# MySensors_PIR.net
KiCad netlist of a schematic drawn in EAGLE
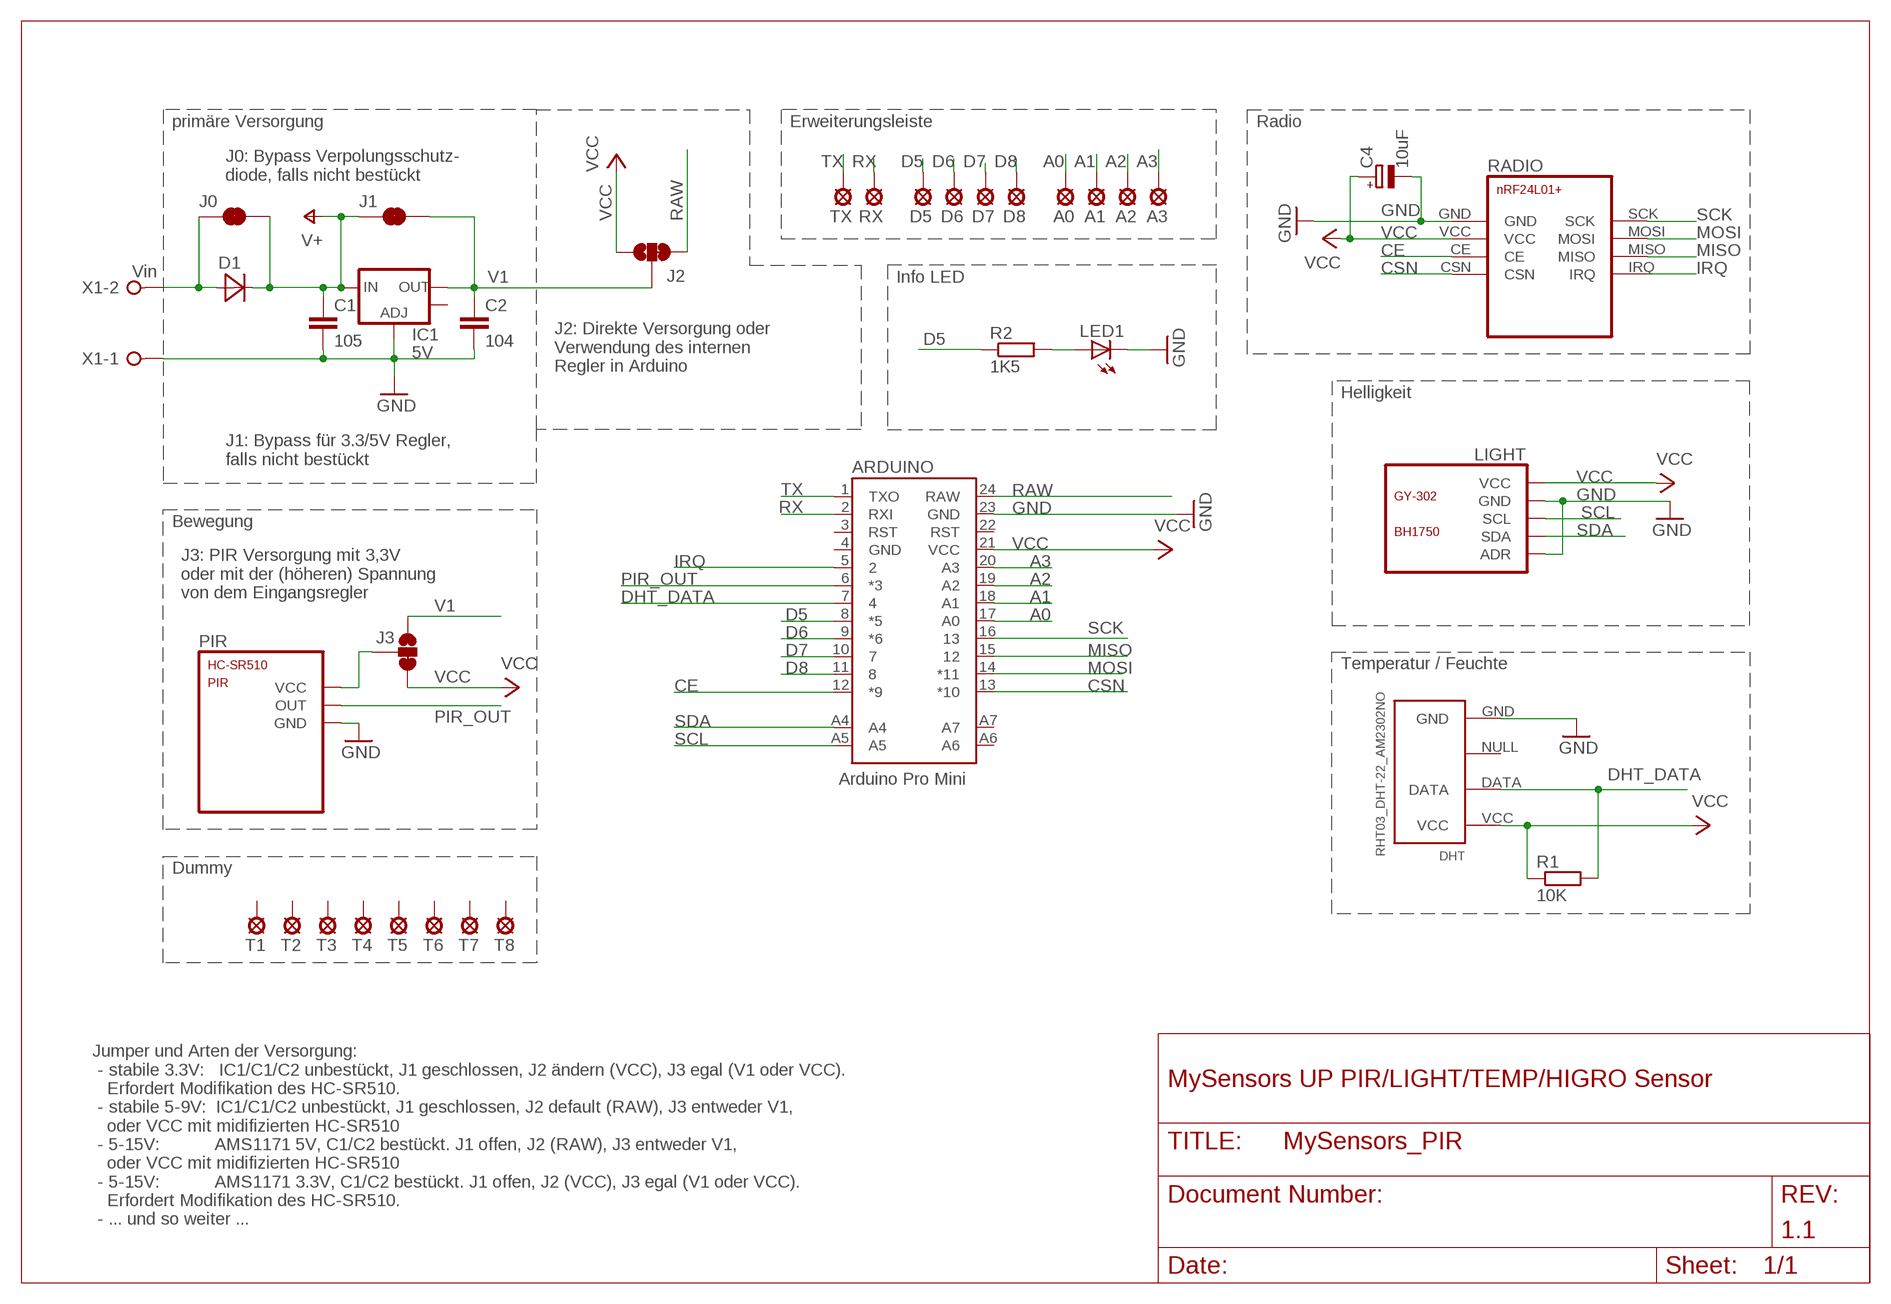
[diagram p0: schematic, sheet 1]

(export (version "E")
  (design (tool "Eeschema 10.0.6"))
  (components
    (comp (ref "A0")
      (value "LSP10")
      (footprint "eagle-import:LSP10")
      (libsource (lib "eagle-import") (part "LSP10"))
    )
    (comp (ref "A1")
      (value "LSP10")
      (footprint "eagle-import:LSP10")
      (libsource (lib "eagle-import") (part "LSP10"))
    )
    (comp (ref "A2")
      (value "LSP10")
      (footprint "eagle-import:LSP10")
      (libsource (lib "eagle-import") (part "LSP10"))
    )
    (comp (ref "A3")
      (value "LSP10")
      (footprint "eagle-import:LSP10")
      (libsource (lib "eagle-import") (part "LSP10"))
    )
    (comp (ref "ARDUINO")
      (value "ARDUINO_PRO_MININO")
      (footprint "eagle-import:ARDUINO_PRO_MINI_O")
      (libsource (lib "eagle-import") (part "ARDUINO_PRO_MININO"))
    )
    (comp (ref "C1")
      (value "105")
      (footprint "eagle-import:C025-025X050")
      (libsource (lib "eagle-import") (part "C-EU025-025X050"))
    )
    (comp (ref "C2")
      (value "104")
      (footprint "eagle-import:C025-025X050")
      (libsource (lib "eagle-import") (part "C-EU025-025X050"))
    )
    (comp (ref "C4")
      (value "10uF")
      (footprint "eagle-import:E2,5-6E")
      (libsource (lib "eagle-import") (part "CPOL-EUE2,5-6E"))
    )
    (comp (ref "D1")
      (value "DIODE2.5U")
      (footprint "eagle-import:DIODE2.5U")
      (libsource (lib "eagle-import") (part "DIODE2.5U"))
    )
    (comp (ref "D5")
      (value "LSP10")
      (footprint "eagle-import:LSP10")
      (libsource (lib "eagle-import") (part "LSP10"))
    )
    (comp (ref "D6")
      (value "LSP10")
      (footprint "eagle-import:LSP10")
      (libsource (lib "eagle-import") (part "LSP10"))
    )
    (comp (ref "D7")
      (value "LSP10")
      (footprint "eagle-import:LSP10")
      (libsource (lib "eagle-import") (part "LSP10"))
    )
    (comp (ref "D8")
      (value "LSP10")
      (footprint "eagle-import:LSP10")
      (libsource (lib "eagle-import") (part "LSP10"))
    )
    (comp (ref "DHT")
      (value "RHT03_DHT-22_AM2302NO")
      (footprint "eagle-import:RHT03_DHT-22_RA_O")
      (libsource (lib "eagle-import") (part "RHT03_DHT-22_AM2302NO"))
    )
    (comp (ref "IC1")
      (value "5V")
      (footprint "eagle-import:SOT223")
      (libsource (lib "eagle-import") (part "V_REG_LM1117SOT223"))
    )
    (comp (ref "J0")
      (value "JUMPER-PAD-2-NC_BY_TRACE")
      (footprint "eagle-import:PAD-JUMPER-2-NC_BY_TRACE_YES_SILK")
      (libsource (lib "eagle-import") (part "JUMPER-PAD-2-NC_BY_TRACE"))
    )
    (comp (ref "J1")
      (value "JUMPER-PAD-2-NC_BY_TRACE")
      (footprint "eagle-import:PAD-JUMPER-2-NC_BY_TRACE_YES_SILK")
      (libsource (lib "eagle-import") (part "JUMPER-PAD-2-NC_BY_TRACE"))
    )
    (comp (ref "J2")
      (value "JUMPER-PAD-3-2OF3_NC_BY_TRACE_SMALL")
      (footprint "eagle-import:PAD-JUMPER-3-2OF3_NC_BY_TRACE_YES_SILK_FULL_BOX")
      (libsource (lib "eagle-import") (part "JUMPER-PAD-3-2OF3_NC_BY_TRACE_SMALL"))
    )
    (comp (ref "J3")
      (value "JUMPER-PAD-3-2OF3_NC_BY_TRACE_SMALL")
      (footprint "eagle-import:PAD-JUMPER-3-2OF3_NC_BY_TRACE_YES_SILK_FULL_BOX")
      (libsource (lib "eagle-import") (part "JUMPER-PAD-3-2OF3_NC_BY_TRACE_SMALL"))
    )
    (comp (ref "LED1")
      (value "UNI_LED_3MM+SMD")
      (footprint "eagle-import:LED3MM")
      (libsource (lib "eagle-import") (part "UNI_LED_3MM+SMD"))
    )
    (comp (ref "LIGHT")
      (value "GY-302")
      (footprint "eagle-import:GY-302")
      (libsource (lib "eagle-import") (part "GY-302"))
    )
    (comp (ref "PIR")
      (value "HC-SR501")
      (footprint "eagle-import:HC-SR501")
      (libsource (lib "eagle-import") (part "HC-SR501"))
    )
    (comp (ref "R1")
      (value "10K")
      (footprint "eagle-import:0204V")
      (libsource (lib "eagle-import") (part "R-EU_0204/2V"))
    )
    (comp (ref "R2")
      (value "1K5")
      (footprint "eagle-import:0204V")
      (libsource (lib "eagle-import") (part "R-EU_0204/2V"))
    )
    (comp (ref "RADIO")
      (value "NRF24L01+")
      (footprint "eagle-import:NRF24L01+")
      (libsource (lib "eagle-import") (part "NRF24L01+"))
    )
    (comp (ref "RX")
      (value "LSP10")
      (footprint "eagle-import:LSP10")
      (libsource (lib "eagle-import") (part "LSP10"))
    )
    (comp (ref "T1")
      (value "LSP10")
      (footprint "eagle-import:LSP10")
      (libsource (lib "eagle-import") (part "LSP10"))
    )
    (comp (ref "T2")
      (value "LSP10")
      (footprint "eagle-import:LSP10")
      (libsource (lib "eagle-import") (part "LSP10"))
    )
    (comp (ref "T3")
      (value "LSP10")
      (footprint "eagle-import:LSP10")
      (libsource (lib "eagle-import") (part "LSP10"))
    )
    (comp (ref "T4")
      (value "LSP10")
      (footprint "eagle-import:LSP10")
      (libsource (lib "eagle-import") (part "LSP10"))
    )
    (comp (ref "T5")
      (value "LSP10")
      (footprint "eagle-import:LSP10")
      (libsource (lib "eagle-import") (part "LSP10"))
    )
    (comp (ref "T6")
      (value "LSP10")
      (footprint "eagle-import:LSP10")
      (libsource (lib "eagle-import") (part "LSP10"))
    )
    (comp (ref "T7")
      (value "LSP10")
      (footprint "eagle-import:LSP10")
      (libsource (lib "eagle-import") (part "LSP10"))
    )
    (comp (ref "T8")
      (value "LSP10")
      (footprint "eagle-import:LSP10")
      (libsource (lib "eagle-import") (part "LSP10"))
    )
    (comp (ref "TX")
      (value "LSP10")
      (footprint "eagle-import:LSP10")
      (libsource (lib "eagle-import") (part "LSP10"))
    )
    (comp (ref "X1")
      (value "Vin")
      (footprint "eagle-import:W237-132")
      (libsource (lib "eagle-import") (part "W237-02P"))
    )
  )
  (nets
    (net (code "1") (name "/A0") (class "Default")
      (node (ref "A0") (pin "1") (pinfunction "MP_1") (pintype "passive"))
      (node (ref "ARDUINO") (pin "17") (pinfunction "A0_17") (pintype "bidirectional"))
    )
    (net (code "2") (name "/A1") (class "Default")
      (node (ref "A1") (pin "1") (pinfunction "MP_1") (pintype "passive"))
      (node (ref "ARDUINO") (pin "18") (pinfunction "A1_18") (pintype "bidirectional"))
    )
    (net (code "3") (name "/A2") (class "Default")
      (node (ref "A2") (pin "1") (pinfunction "MP_1") (pintype "passive"))
      (node (ref "ARDUINO") (pin "19") (pinfunction "A2_19") (pintype "bidirectional"))
    )
    (net (code "4") (name "/A3") (class "Default")
      (node (ref "A3") (pin "1") (pinfunction "MP_1") (pintype "passive"))
      (node (ref "ARDUINO") (pin "20") (pinfunction "A3_20") (pintype "bidirectional"))
    )
    (net (code "5") (name "/CE") (class "Default")
      (node (ref "ARDUINO") (pin "12") (pinfunction "*9_12") (pintype "bidirectional"))
      (node (ref "RADIO") (pin "CE") (pinfunction "CE_CE") (pintype "bidirectional"))
    )
    (net (code "6") (name "/CSN") (class "Default")
      (node (ref "ARDUINO") (pin "13") (pinfunction "*10_13") (pintype "bidirectional"))
      (node (ref "RADIO") (pin "CSN") (pinfunction "CSN_CSN") (pintype "bidirectional"))
    )
    (net (code "7") (name "/D5") (class "Default")
      (node (ref "ARDUINO") (pin "8") (pinfunction "*5_8") (pintype "bidirectional"))
      (node (ref "D5") (pin "1") (pinfunction "MP_1") (pintype "passive"))
      (node (ref "R2") (pin "1") (pinfunction "1_1") (pintype "passive"))
    )
    (net (code "8") (name "/D6") (class "Default")
      (node (ref "ARDUINO") (pin "9") (pinfunction "*6_9") (pintype "bidirectional"))
      (node (ref "D6") (pin "1") (pinfunction "MP_1") (pintype "passive"))
    )
    (net (code "9") (name "/D7") (class "Default")
      (node (ref "ARDUINO") (pin "10") (pinfunction "7_10") (pintype "bidirectional"))
      (node (ref "D7") (pin "1") (pinfunction "MP_1") (pintype "passive"))
    )
    (net (code "10") (name "/D8") (class "Default")
      (node (ref "ARDUINO") (pin "11") (pinfunction "8_11") (pintype "bidirectional"))
      (node (ref "D8") (pin "1") (pinfunction "MP_1") (pintype "passive"))
    )
    (net (code "11") (name "/DHT_DATA") (class "Default")
      (node (ref "ARDUINO") (pin "7") (pinfunction "4_7") (pintype "bidirectional"))
      (node (ref "DHT") (pin "DATA") (pinfunction "DATA_DATA") (pintype "bidirectional"))
      (node (ref "R1") (pin "2") (pinfunction "2_2") (pintype "passive"))
    )
    (net (code "12") (name "/IRQ") (class "Default")
      (node (ref "ARDUINO") (pin "5") (pinfunction "2_5") (pintype "bidirectional"))
      (node (ref "RADIO") (pin "IRQ") (pinfunction "IRQ_IRQ") (pintype "bidirectional"))
    )
    (net (code "13") (name "/MISO") (class "Default")
      (node (ref "ARDUINO") (pin "15") (pinfunction "12_15") (pintype "bidirectional"))
      (node (ref "RADIO") (pin "MISO") (pinfunction "MISO_MISO") (pintype "bidirectional"))
    )
    (net (code "14") (name "/MOSI") (class "Default")
      (node (ref "ARDUINO") (pin "14") (pinfunction "*11_14") (pintype "bidirectional"))
      (node (ref "RADIO") (pin "MOSI") (pinfunction "MOSI_MOSI") (pintype "bidirectional"))
    )
    (net (code "15") (name "/PIR_OUT") (class "Default")
      (node (ref "ARDUINO") (pin "6") (pinfunction "*3_6") (pintype "bidirectional"))
      (node (ref "PIR") (pin "OUT") (pinfunction "OUT_OUT") (pintype "bidirectional"))
    )
    (net (code "16") (name "/RAW") (class "Default")
      (node (ref "ARDUINO") (pin "24") (pinfunction "RAW_24") (pintype "bidirectional"))
      (node (ref "J2") (pin "3") (pinfunction "3_3") (pintype "passive"))
    )
    (net (code "17") (name "/RX") (class "Default")
      (node (ref "ARDUINO") (pin "2") (pinfunction "RXI_2") (pintype "bidirectional"))
      (node (ref "RX") (pin "1") (pinfunction "MP_1") (pintype "passive"))
    )
    (net (code "18") (name "/SCK") (class "Default")
      (node (ref "ARDUINO") (pin "16") (pinfunction "13_16") (pintype "bidirectional"))
      (node (ref "RADIO") (pin "SCK") (pinfunction "SCK_SCK") (pintype "bidirectional"))
    )
    (net (code "19") (name "/SCL") (class "Default")
      (node (ref "ARDUINO") (pin "A5") (pinfunction "A5_A5") (pintype "bidirectional"))
      (node (ref "LIGHT") (pin "SCL") (pinfunction "SCL_SCL") (pintype "bidirectional"))
    )
    (net (code "20") (name "/SDA") (class "Default")
      (node (ref "ARDUINO") (pin "A4") (pinfunction "A4_A4") (pintype "bidirectional"))
      (node (ref "LIGHT") (pin "SDA") (pinfunction "SDA_SDA") (pintype "bidirectional"))
    )
    (net (code "21") (name "/TX") (class "Default")
      (node (ref "ARDUINO") (pin "1") (pinfunction "TXO_1") (pintype "bidirectional"))
      (node (ref "TX") (pin "1") (pinfunction "MP_1") (pintype "passive"))
    )
    (net (code "22") (name "/V1") (class "Default")
      (node (ref "C2") (pin "1") (pinfunction "1_1") (pintype "passive"))
      (node (ref "IC1") (pin "2") (pinfunction "OUT_2") (pintype "output"))
      (node (ref "J1") (pin "2") (pinfunction "2_2") (pintype "passive"))
      (node (ref "J2") (pin "2") (pinfunction "2_2") (pintype "passive"))
      (node (ref "J3") (pin "1") (pinfunction "1_1") (pintype "passive"))
    )
    (net (code "23") (name "GND") (class "Default")
      (node (ref "ARDUINO") (pin "23") (pinfunction "GND_23") (pintype "bidirectional"))
      (node (ref "C1") (pin "2") (pinfunction "2_2") (pintype "passive"))
      (node (ref "C2") (pin "2") (pinfunction "2_2") (pintype "passive"))
      (node (ref "C4") (pin "-") (pinfunction "-_-") (pintype "passive"))
      (node (ref "DHT") (pin "GND") (pinfunction "GND_GND") (pintype "power_in"))
      (node (ref "IC1") (pin "1") (pinfunction "ADJ_1") (pintype "input"))
      (node (ref "LED1") (pin "K") (pinfunction "C_K") (pintype "passive"))
      (node (ref "LIGHT") (pin "ADR") (pinfunction "ADR_ADR") (pintype "input"))
      (node (ref "LIGHT") (pin "GND") (pinfunction "GND_GND") (pintype "power_in"))
      (node (ref "PIR") (pin "GND") (pinfunction "GND_GND") (pintype "power_in"))
      (node (ref "RADIO") (pin "GND") (pinfunction "GND_GND") (pintype "power_in"))
      (node (ref "X1") (pin "1") (pinfunction "KL_1") (pintype "passive"))
    )
    (net (code "24") (name "Net-(J3-Pad2)") (class "Default")
      (node (ref "J3") (pin "2") (pinfunction "2_2") (pintype "passive"))
      (node (ref "PIR") (pin "VCC") (pinfunction "VCC_VCC") (pintype "power_in"))
    )
    (net (code "25") (name "Net-(LED1-PadA)") (class "Default")
      (node (ref "LED1") (pin "A") (pinfunction "A_A") (pintype "passive"))
      (node (ref "R2") (pin "2") (pinfunction "2_2") (pintype "passive"))
    )
    (net (code "26") (name "Net-(X1B-KL)") (class "Default")
      (node (ref "D1") (pin "A") (pinfunction "A_A") (pintype "passive"))
      (node (ref "J0") (pin "1") (pinfunction "1_1") (pintype "passive"))
      (node (ref "X1") (pin "2") (pinfunction "KL_2") (pintype "passive"))
    )
    (net (code "27") (name "V+") (class "Default")
      (node (ref "C1") (pin "1") (pinfunction "1_1") (pintype "passive"))
      (node (ref "D1") (pin "K") (pinfunction "C_K") (pintype "passive"))
      (node (ref "IC1") (pin "3") (pinfunction "IN_3") (pintype "input"))
      (node (ref "J0") (pin "2") (pinfunction "2_2") (pintype "passive"))
      (node (ref "J1") (pin "1") (pinfunction "1_1") (pintype "passive"))
    )
    (net (code "28") (name "VCC") (class "Default")
      (node (ref "ARDUINO") (pin "21") (pinfunction "VCC_21") (pintype "bidirectional"))
      (node (ref "C4") (pin "+") (pinfunction "+_+") (pintype "passive"))
      (node (ref "DHT") (pin "VCC") (pinfunction "VCC_VCC") (pintype "power_in"))
      (node (ref "J2") (pin "1") (pinfunction "1_1") (pintype "passive"))
      (node (ref "J3") (pin "3") (pinfunction "3_3") (pintype "passive"))
      (node (ref "LIGHT") (pin "VCC") (pinfunction "VCC_VCC") (pintype "power_in"))
      (node (ref "R1") (pin "1") (pinfunction "1_1") (pintype "passive"))
      (node (ref "RADIO") (pin "VCC") (pinfunction "VCC_VCC") (pintype "power_in"))
    )
    (net (code "29") (name "unconnected-(ARDUINO-GND-Pad4)") (class "Default")
      (node (ref "ARDUINO") (pin "4") (pinfunction "GND_4") (pintype "bidirectional"))
    )
    (net (code "30") (name "unconnected-(ARDUINO-PadA6)") (class "Default")
      (node (ref "ARDUINO") (pin "A6") (pinfunction "A6_A6") (pintype "bidirectional"))
    )
    (net (code "31") (name "unconnected-(ARDUINO-PadA7)") (class "Default")
      (node (ref "ARDUINO") (pin "A7") (pinfunction "A7_A7") (pintype "bidirectional"))
    )
    (net (code "32") (name "unconnected-(ARDUINO-RST-Pad3)") (class "Default")
      (node (ref "ARDUINO") (pin "3") (pinfunction "RST_3") (pintype "bidirectional"))
    )
    (net (code "33") (name "unconnected-(ARDUINO-RST-Pad22)") (class "Default")
      (node (ref "ARDUINO") (pin "22") (pinfunction "RST_22") (pintype "bidirectional"))
    )
    (net (code "34") (name "unconnected-(DHT-PadNULL)") (class "Default")
      (node (ref "DHT") (pin "NULL") (pinfunction "NULL_NULL") (pintype "no_connect"))
    )
    (net (code "35") (name "unconnected-(IC1-OUT-Pad4)") (class "Default")
      (node (ref "IC1") (pin "4") (pinfunction "OUT_4") (pintype "output"))
    )
    (net (code "36") (name "unconnected-(T1-MP-Pad1)") (class "Default")
      (node (ref "T1") (pin "1") (pinfunction "MP_1") (pintype "passive"))
    )
    (net (code "37") (name "unconnected-(T2-MP-Pad1)") (class "Default")
      (node (ref "T2") (pin "1") (pinfunction "MP_1") (pintype "passive"))
    )
    (net (code "38") (name "unconnected-(T3-MP-Pad1)") (class "Default")
      (node (ref "T3") (pin "1") (pinfunction "MP_1") (pintype "passive"))
    )
    (net (code "39") (name "unconnected-(T4-MP-Pad1)") (class "Default")
      (node (ref "T4") (pin "1") (pinfunction "MP_1") (pintype "passive"))
    )
    (net (code "40") (name "unconnected-(T5-MP-Pad1)") (class "Default")
      (node (ref "T5") (pin "1") (pinfunction "MP_1") (pintype "passive"))
    )
    (net (code "41") (name "unconnected-(T6-MP-Pad1)") (class "Default")
      (node (ref "T6") (pin "1") (pinfunction "MP_1") (pintype "passive"))
    )
    (net (code "42") (name "unconnected-(T7-MP-Pad1)") (class "Default")
      (node (ref "T7") (pin "1") (pinfunction "MP_1") (pintype "passive"))
    )
    (net (code "43") (name "unconnected-(T8-MP-Pad1)") (class "Default")
      (node (ref "T8") (pin "1") (pinfunction "MP_1") (pintype "passive"))
    )
  )
)
